# Audio.net
KiCad netlist of a schematic drawn in Altium Designer
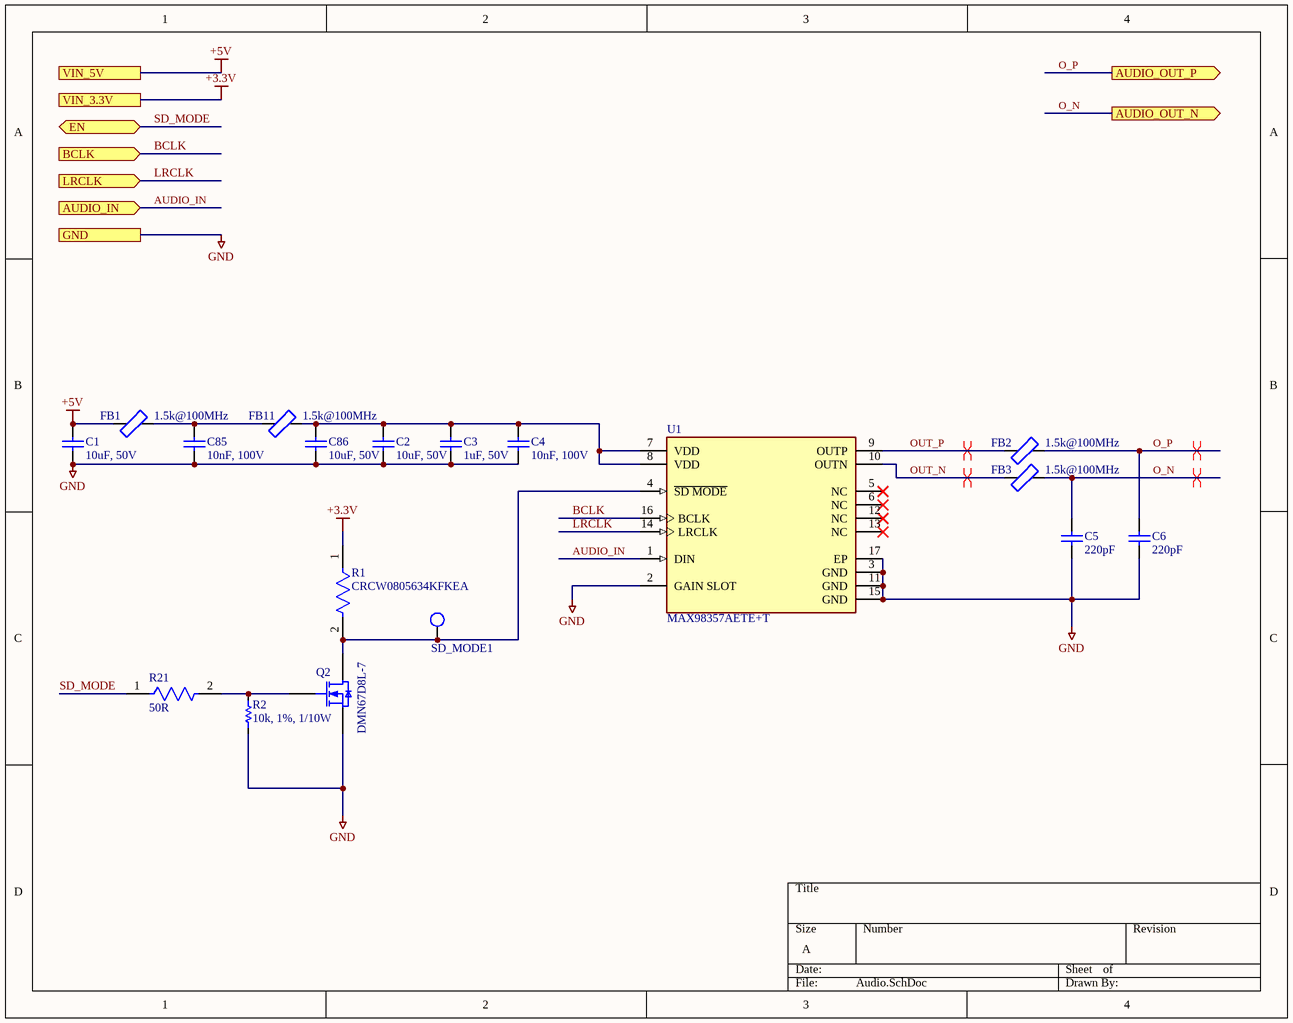
[diagram p0: Audio.SchDoc]

(export (version "E")
  (design (tool "Eeschema 10.0.6"))
  (components
    (comp (ref "C1")
      (value "10uF, 50V")
      (footprint "1206")
      (description "CAP CER 10UF 50V X7R 1206")
      (fields (field (name "PART NUMBER") "NS00832"))
      (libsource (lib "FullPartsDB") (part "Cap"))
    )
    (comp (ref "C2")
      (value "10uF, 50V")
      (footprint "1206")
      (description "CAP CER 10UF 50V X7R 1206")
      (fields (field (name "PART NUMBER") "NS00832"))
      (libsource (lib "FullPartsDB") (part "Cap"))
    )
    (comp (ref "C3")
      (value "1uF, 50V")
      (footprint "0805")
      (description "CAP CER 1UF 50V X7R 0805")
      (fields (field (name "PART NUMBER") "NS00871"))
      (libsource (lib "FullPartsDB") (part "Cap"))
    )
    (comp (ref "C4")
      (value "10nF, 100V")
      (footprint "0603")
      (description "CAP CER 10000PF 100V C0G 0603")
      (fields (field (name "PART NUMBER") "NS00848"))
      (libsource (lib "FullPartsDB") (part "Cap"))
    )
    (comp (ref "C5")
      (value "220pF")
      (footprint "CAPC2013X88X50LL20T25")
      (fields (field (name "PART NUMBER") "C0805C221J2GACTU") (field (name "MANUFACTURER") "Kemet"))
      (libsource (lib "Altium Content Vault") (part "CAP"))
    )
    (comp (ref "C6")
      (value "220pF")
      (footprint "CAPC2013X88X50LL20T25")
      (fields (field (name "PART NUMBER") "C0805C221J2GACTU") (field (name "MANUFACTURER") "Kemet"))
      (libsource (lib "Altium Content Vault") (part "CAP"))
    )
    (comp (ref "C85")
      (value "10nF, 100V")
      (footprint "0603")
      (description "CAP CER 10000PF 100V C0G 0603")
      (fields (field (name "PART NUMBER") "NS00848"))
      (libsource (lib "FullPartsDB") (part "Cap"))
    )
    (comp (ref "C86")
      (value "10uF, 50V")
      (footprint "1206")
      (description "CAP CER 10UF 50V X7R 1206")
      (fields (field (name "PART NUMBER") "NS00832"))
      (libsource (lib "FullPartsDB") (part "Cap"))
    )
    (comp (ref "FB1")
      (value "1.5k@100MHz")
      (footprint "0805")
      (description "WE-CBA SMT EMI SUPPRESSION FERRITE")
      (fields (field (name "PART NUMBER") "NS00881"))
      (libsource (lib "FullPartsDB") (part "Bead"))
    )
    (comp (ref "FB2")
      (value "1.5k@100MHz")
      (footprint "0805")
      (description "WE-CBA SMT EMI SUPPRESSION FERRITE")
      (fields (field (name "PART NUMBER") "NS00881"))
      (libsource (lib "FullPartsDB") (part "Bead"))
    )
    (comp (ref "FB3")
      (value "1.5k@100MHz")
      (footprint "0805")
      (description "WE-CBA SMT EMI SUPPRESSION FERRITE")
      (fields (field (name "PART NUMBER") "NS00881"))
      (libsource (lib "FullPartsDB") (part "Bead"))
    )
    (comp (ref "FB11")
      (value "1.5k@100MHz")
      (footprint "0805")
      (description "WE-CBA SMT EMI SUPPRESSION FERRITE")
      (fields (field (name "PART NUMBER") "NS00881"))
      (libsource (lib "FullPartsDB") (part "Bead"))
    )
    (comp (ref "Q2")
      (value "DMN67D8L-7")
      (footprint "SOT23-3")
      (description "MOSFET N-CH 60V 210MA SOT23")
      (fields (field (name "PART NUMBER") "NS00873") (field (name "PUBLISHER") "Altium Limited"))
      (libsource (lib "FullPartsDB") (part "FET_N_GSD"))
    )
    (comp (ref "R1")
      (value "CRCW0805634KFKEA")
      (footprint "FP-CRCW0805-e3-MFG")
      (description "RES Thick Film, 634kΩ, 1%, 0.125W, 100ppm/°C, 0805")
      (fields (field (name "TOLERANCE") "1%"))
      (libsource (lib "Altium Content Vault") (part "1029c3af85768c4190bb7ad29bc67b5"))
    )
    (comp (ref "R2")
      (value "10k, 1%, 1/10W")
      (footprint "0603")
      (description "RES 10K OHM 1% 1/10W 0603")
      (fields (field (name "PART NUMBER") "NS00820"))
      (libsource (lib "FullPartsDB") (part "RESISTOR"))
    )
    (comp (ref "R21")
      (value "50R")
      (footprint "FP-RCP0603W-MFG")
      (description "RES SMD 50 OHM 2% 1.5W 0603")
      (fields (field (name "TOLERANCE") "2%"))
      (libsource (lib "Altium Content Vault") (part "1029c3af85768c4190bb7ad29bc67b5"))
    )
    (comp (ref "SD_MODE1")
      (value "2mm")
      (footprint "TEST POINT 40 Mil")
      (description "Testpoint 2mm round")
      (fields (field (name "PART NUMBER") "NS00254"))
      (libsource (lib "FullPartsDB") (part "TESTPOINT"))
    )
    (comp (ref "U1")
      (value "MAX98357AETE+T")
      (footprint "FP-T1633-4-MFG")
      (description "IC AMP CLASS D MONO 3.2W 16TQFN")
      (libsource (lib "Altium Content Vault") (part "902df0143a84dfa2dd990dcc5368a09"))
    )
  )
  (nets
    (net (code "1") (name "+3.3V") (class "Default")
      (node (ref "R1") (pin "1") (pinfunction "1_1") (pintype "passive"))
    )
    (net (code "2") (name "+5V") (class "Default")
      (node (ref "C1") (pin "2") (pinfunction "2_2") (pintype "passive"))
      (node (ref "FB1") (pin "1") (pinfunction "1_1") (pintype "passive"))
    )
    (net (code "3") (name "/AUDIO_IN") (class "Default")
      (node (ref "U1") (pin "1") (pinfunction "DIN_1") (pintype "input"))
    )
    (net (code "4") (name "/BCLK") (class "Default")
      (node (ref "U1") (pin "16") (pinfunction "BCLK_16") (pintype "input"))
    )
    (net (code "5") (name "/LRCLK") (class "Default")
      (node (ref "U1") (pin "14") (pinfunction "LRCLK_14") (pintype "input"))
    )
    (net (code "6") (name "/OUT_N") (class "Default")
      (node (ref "FB3") (pin "1") (pinfunction "1_1") (pintype "passive"))
      (node (ref "U1") (pin "10") (pinfunction "OUTN_10") (pintype "passive"))
    )
    (net (code "7") (name "/OUT_P") (class "Default")
      (node (ref "FB2") (pin "1") (pinfunction "1_1") (pintype "passive"))
      (node (ref "U1") (pin "9") (pinfunction "OUTP_9") (pintype "passive"))
    )
    (net (code "8") (name "/O_N") (class "Default")
      (node (ref "C5") (pin "2") (pinfunction "2_2") (pintype "passive"))
      (node (ref "FB3") (pin "2") (pinfunction "2_2") (pintype "passive"))
    )
    (net (code "9") (name "/O_P") (class "Default")
      (node (ref "C6") (pin "2") (pinfunction "2_2") (pintype "passive"))
      (node (ref "FB2") (pin "2") (pinfunction "2_2") (pintype "passive"))
    )
    (net (code "10") (name "/SD_MODE") (class "Default")
      (node (ref "R21") (pin "1") (pinfunction "1_1") (pintype "passive"))
    )
    (net (code "11") (name "GND") (class "Default")
      (node (ref "C1") (pin "1") (pinfunction "1_1") (pintype "passive"))
      (node (ref "C2") (pin "1") (pinfunction "1_1") (pintype "passive"))
      (node (ref "C3") (pin "1") (pinfunction "1_1") (pintype "passive"))
      (node (ref "C4") (pin "2") (pinfunction "2_2") (pintype "passive"))
      (node (ref "C5") (pin "1") (pinfunction "1_1") (pintype "passive"))
      (node (ref "C6") (pin "1") (pinfunction "1_1") (pintype "passive"))
      (node (ref "C85") (pin "2") (pinfunction "2_2") (pintype "passive"))
      (node (ref "C86") (pin "1") (pinfunction "1_1") (pintype "passive"))
      (node (ref "Q2") (pin "2") (pinfunction "S_2") (pintype "passive"))
      (node (ref "R2") (pin "2") (pinfunction "2_2") (pintype "passive"))
      (node (ref "U1") (pin "11") (pinfunction "GND_11") (pintype "power_in"))
      (node (ref "U1") (pin "15") (pinfunction "GND_15") (pintype "power_in"))
      (node (ref "U1") (pin "17") (pinfunction "EP_17") (pintype "passive"))
      (node (ref "U1") (pin "2") (pinfunction "GAIN_SLOT_2") (pintype "passive"))
      (node (ref "U1") (pin "3") (pinfunction "GND_3") (pintype "power_in"))
    )
    (net (code "12") (name "Net-(C2-Pad2)") (class "Default")
      (node (ref "C2") (pin "2") (pinfunction "2_2") (pintype "passive"))
      (node (ref "C3") (pin "2") (pinfunction "2_2") (pintype "passive"))
      (node (ref "C4") (pin "1") (pinfunction "1_1") (pintype "passive"))
      (node (ref "C86") (pin "2") (pinfunction "2_2") (pintype "passive"))
      (node (ref "FB11") (pin "2") (pinfunction "2_2") (pintype "passive"))
      (node (ref "U1") (pin "7") (pinfunction "VDD_7") (pintype "power_in"))
      (node (ref "U1") (pin "8") (pinfunction "VDD_8") (pintype "power_in"))
    )
    (net (code "13") (name "Net-(C85-Pad1)") (class "Default")
      (node (ref "C85") (pin "1") (pinfunction "1_1") (pintype "passive"))
      (node (ref "FB1") (pin "2") (pinfunction "2_2") (pintype "passive"))
      (node (ref "FB11") (pin "1") (pinfunction "1_1") (pintype "passive"))
    )
    (net (code "14") (name "Net-(Q2-D)") (class "Default")
      (node (ref "Q2") (pin "3") (pinfunction "D_3") (pintype "passive"))
      (node (ref "R1") (pin "2") (pinfunction "2_2") (pintype "passive"))
      (node (ref "SD_MODE1") (pin "1") (pinfunction "TP_1") (pintype "passive"))
      (node (ref "U1") (pin "4") (pinfunction "~{SD_MODE}_4") (pintype "input"))
    )
    (net (code "15") (name "Net-(Q2-G)") (class "Default")
      (node (ref "Q2") (pin "1") (pinfunction "G_1") (pintype "passive"))
      (node (ref "R2") (pin "1") (pinfunction "1_1") (pintype "passive"))
      (node (ref "R21") (pin "2") (pinfunction "2_2") (pintype "passive"))
    )
    (net (code "16") (name "unconnected-(U1-NC-Pad5)") (class "Default")
      (node (ref "U1") (pin "5") (pinfunction "NC_5") (pintype "passive+no_connect"))
    )
    (net (code "17") (name "unconnected-(U1-NC-Pad6)") (class "Default")
      (node (ref "U1") (pin "6") (pinfunction "NC_6") (pintype "passive+no_connect"))
    )
    (net (code "18") (name "unconnected-(U1-NC-Pad12)") (class "Default")
      (node (ref "U1") (pin "12") (pinfunction "NC_12") (pintype "passive+no_connect"))
    )
    (net (code "19") (name "unconnected-(U1-NC-Pad13)") (class "Default")
      (node (ref "U1") (pin "13") (pinfunction "NC_13") (pintype "passive+no_connect"))
    )
  )
)
